# PGA-103_LNA_Mod2.net
KiCad netlist of a schematic drawn in EAGLE
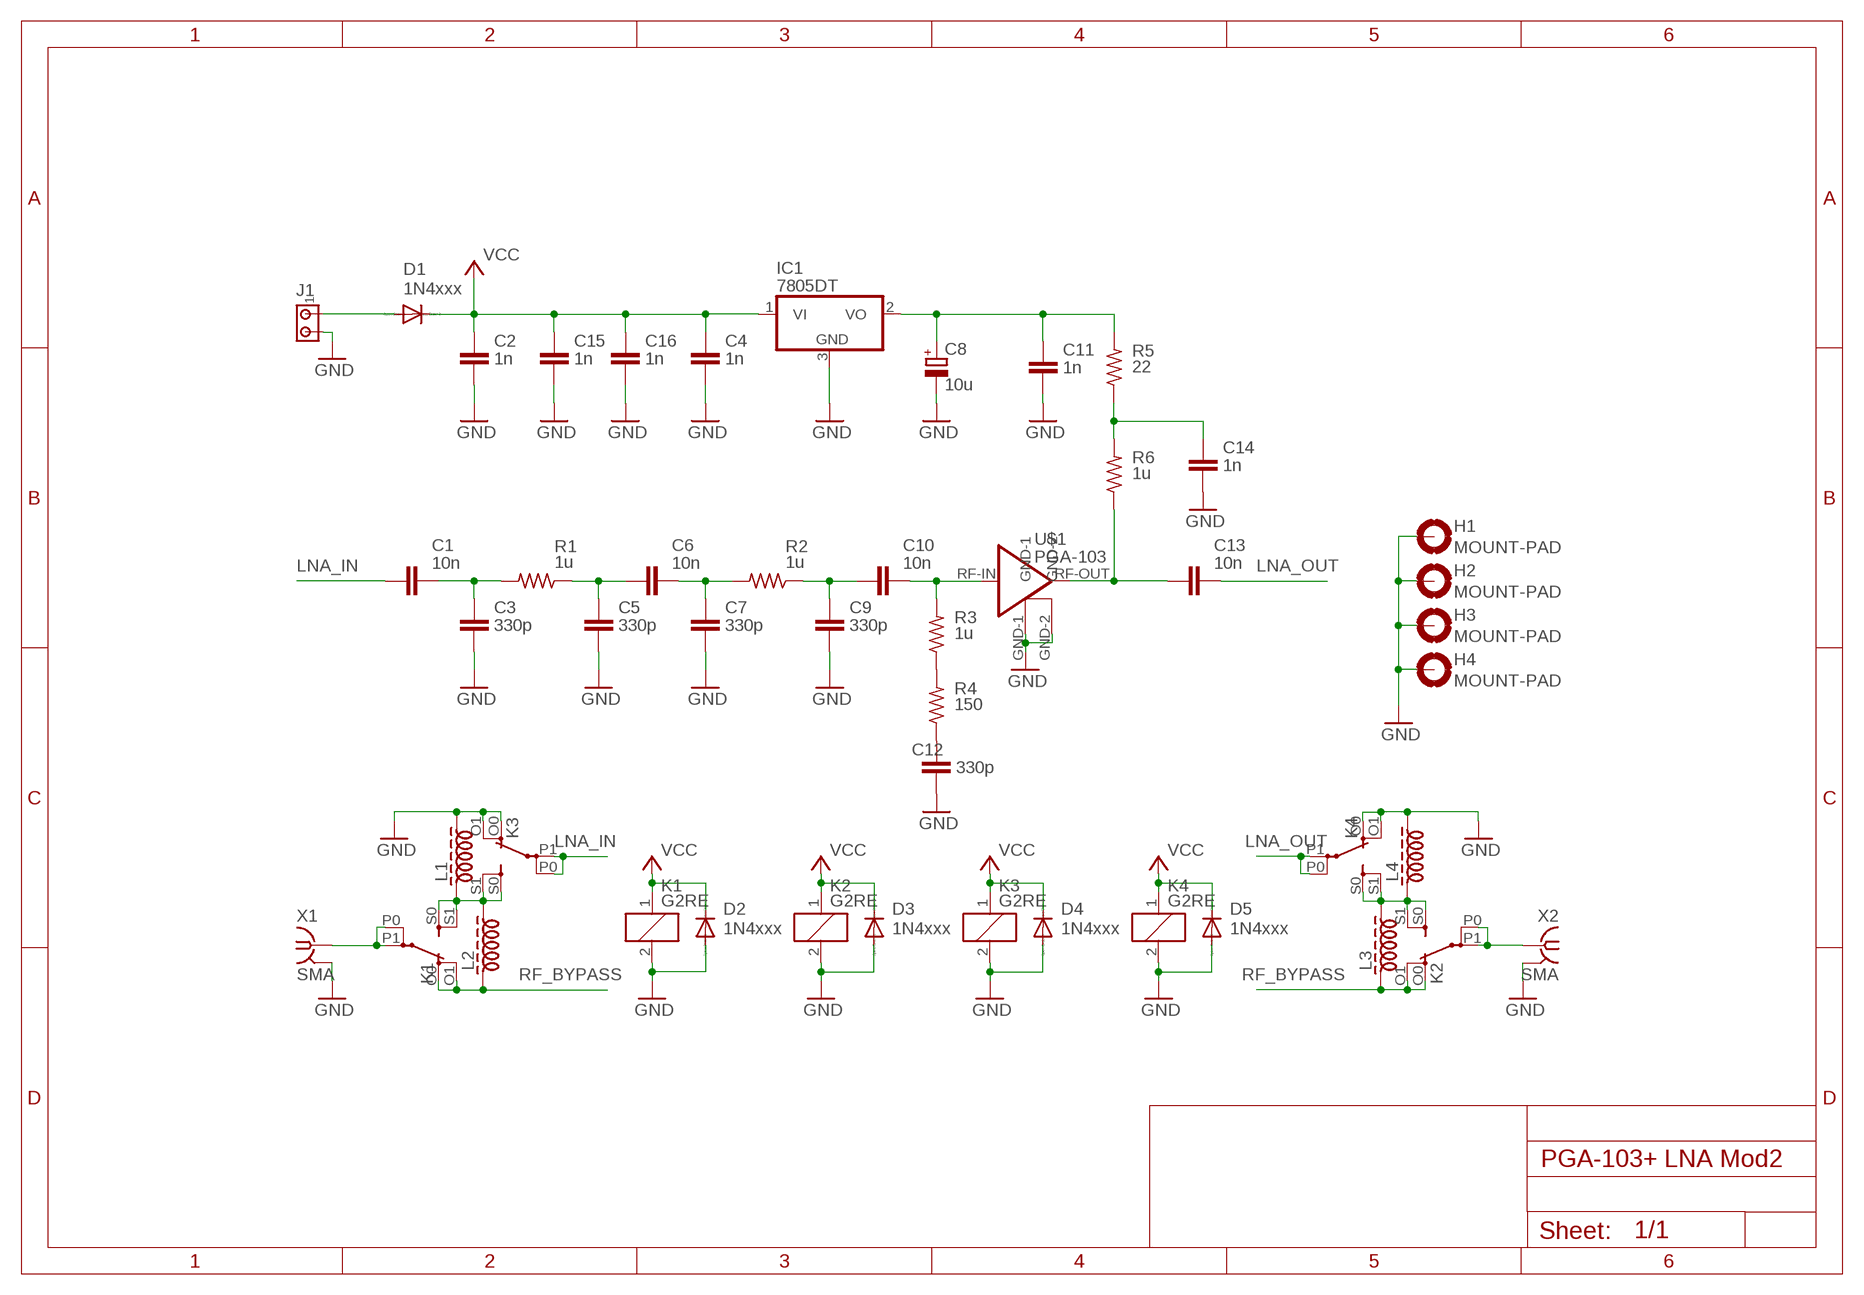
[diagram p0: schematic, sheet 1]

(export (version "E")
  (design (tool "Eeschema 10.0.6"))
  (components
    (comp (ref "C1")
      (value "10n")
      (footprint "eagle-import:C1206")
      (libsource (lib "eagle-import") (part "C-EUC1206"))
    )
    (comp (ref "C2")
      (value "1n")
      (footprint "eagle-import:C1206")
      (libsource (lib "eagle-import") (part "C-EUC1206"))
    )
    (comp (ref "C3")
      (value "330p")
      (footprint "eagle-import:C1206")
      (libsource (lib "eagle-import") (part "C-EUC1206"))
    )
    (comp (ref "C4")
      (value "1n")
      (footprint "eagle-import:C1206")
      (libsource (lib "eagle-import") (part "C-EUC1206"))
    )
    (comp (ref "C5")
      (value "330p")
      (footprint "eagle-import:C1206")
      (libsource (lib "eagle-import") (part "C-EUC1206"))
    )
    (comp (ref "C6")
      (value "10n")
      (footprint "eagle-import:C1206")
      (libsource (lib "eagle-import") (part "C-EUC1206"))
    )
    (comp (ref "C7")
      (value "330p")
      (footprint "eagle-import:C1206")
      (libsource (lib "eagle-import") (part "C-EUC1206"))
    )
    (comp (ref "C8")
      (value "10u")
      (footprint "eagle-import:B_3528-21R")
      (libsource (lib "eagle-import") (part "CPOL-EUB/3528-21R"))
    )
    (comp (ref "C9")
      (value "330p")
      (footprint "eagle-import:C1206")
      (libsource (lib "eagle-import") (part "C-EUC1206"))
    )
    (comp (ref "C10")
      (value "10n")
      (footprint "eagle-import:C1206")
      (libsource (lib "eagle-import") (part "C-EUC1206"))
    )
    (comp (ref "C11")
      (value "1n")
      (footprint "eagle-import:C1206")
      (libsource (lib "eagle-import") (part "C-EUC1206"))
    )
    (comp (ref "C12")
      (value "330p")
      (footprint "eagle-import:C1206")
      (libsource (lib "eagle-import") (part "C-EUC1206"))
    )
    (comp (ref "C13")
      (value "10n")
      (footprint "eagle-import:C1206")
      (libsource (lib "eagle-import") (part "C-EUC1206"))
    )
    (comp (ref "C14")
      (value "1n")
      (footprint "eagle-import:C1206")
      (libsource (lib "eagle-import") (part "C-EUC1206"))
    )
    (comp (ref "C15")
      (value "1n")
      (footprint "eagle-import:C1206")
      (libsource (lib "eagle-import") (part "C-EUC1206"))
    )
    (comp (ref "C16")
      (value "1n")
      (footprint "eagle-import:C1206")
      (libsource (lib "eagle-import") (part "C-EUC1206"))
    )
    (comp (ref "D1")
      (value "1N4xxx")
      (footprint "eagle-import:DO35-7")
      (libsource (lib "eagle-import") (part "1N4148DO35-7"))
    )
    (comp (ref "D2")
      (value "1N4xxx")
      (footprint "eagle-import:DO35-7")
      (libsource (lib "eagle-import") (part "1N4148DO35-7"))
    )
    (comp (ref "D3")
      (value "1N4xxx")
      (footprint "eagle-import:DO35-7")
      (libsource (lib "eagle-import") (part "1N4148DO35-7"))
    )
    (comp (ref "D4")
      (value "1N4xxx")
      (footprint "eagle-import:DO35-7")
      (libsource (lib "eagle-import") (part "1N4148DO35-7"))
    )
    (comp (ref "D5")
      (value "1N4xxx")
      (footprint "eagle-import:DO35-7")
      (libsource (lib "eagle-import") (part "1N4148DO35-7"))
    )
    (comp (ref "H1")
      (value "MOUNT-PAD")
      (footprint "eagle-import:2,8-PAD")
      (libsource (lib "eagle-import") (part "MOUNT-PAD-ROUND2.8"))
    )
    (comp (ref "H2")
      (value "MOUNT-PAD")
      (footprint "eagle-import:2,8-PAD")
      (libsource (lib "eagle-import") (part "MOUNT-PAD-ROUND2.8"))
    )
    (comp (ref "H3")
      (value "MOUNT-PAD")
      (footprint "eagle-import:2,8-PAD")
      (libsource (lib "eagle-import") (part "MOUNT-PAD-ROUND2.8"))
    )
    (comp (ref "H4")
      (value "MOUNT-PAD")
      (footprint "eagle-import:2,8-PAD")
      (libsource (lib "eagle-import") (part "MOUNT-PAD-ROUND2.8"))
    )
    (comp (ref "IC1")
      (value "7805DT")
      (footprint "eagle-import:TO252")
      (libsource (lib "eagle-import") (part "78DT05"))
    )
    (comp (ref "J1")
      (value "MTA02-156")
      (footprint "eagle-import:1X2MTA")
      (libsource (lib "eagle-import") (part "MTA02-156"))
    )
    (comp (ref "K1")
      (value "G2RE")
      (footprint "eagle-import:G2RE")
      (libsource (lib "eagle-import") (part "G2RE"))
    )
    (comp (ref "K2")
      (value "G2RE")
      (footprint "eagle-import:G2RE")
      (libsource (lib "eagle-import") (part "G2RE"))
    )
    (comp (ref "K3")
      (value "G2RE")
      (footprint "eagle-import:G2RE")
      (libsource (lib "eagle-import") (part "G2RE"))
    )
    (comp (ref "K4")
      (value "G2RE")
      (footprint "eagle-import:G2RE")
      (libsource (lib "eagle-import") (part "G2RE"))
    )
    (comp (ref "L1")
      (value "Z28/70CW")
      (footprint "eagle-import:Z28_7")
      (libsource (lib "eagle-import") (part "Z?CW28/70"))
    )
    (comp (ref "L2")
      (value "Z28/70CW")
      (footprint "eagle-import:Z28_7")
      (libsource (lib "eagle-import") (part "Z?CW28/70"))
    )
    (comp (ref "L3")
      (value "Z28/70CW")
      (footprint "eagle-import:Z28_7")
      (libsource (lib "eagle-import") (part "Z?CW28/70"))
    )
    (comp (ref "L4")
      (value "Z28/70CW")
      (footprint "eagle-import:Z28_7")
      (libsource (lib "eagle-import") (part "Z?CW28/70"))
    )
    (comp (ref "R1")
      (value "1u")
      (footprint "eagle-import:M1206")
      (libsource (lib "eagle-import") (part "R-US_M1206"))
    )
    (comp (ref "R2")
      (value "1u")
      (footprint "eagle-import:M1206")
      (libsource (lib "eagle-import") (part "R-US_M1206"))
    )
    (comp (ref "R3")
      (value "1u")
      (footprint "eagle-import:M1206")
      (libsource (lib "eagle-import") (part "R-US_M1206"))
    )
    (comp (ref "R4")
      (value "150")
      (footprint "eagle-import:M1206")
      (libsource (lib "eagle-import") (part "R-US_M1206"))
    )
    (comp (ref "R5")
      (value "22")
      (footprint "eagle-import:M1206")
      (libsource (lib "eagle-import") (part "R-US_M1206"))
    )
    (comp (ref "R6")
      (value "1u")
      (footprint "eagle-import:M1206")
      (libsource (lib "eagle-import") (part "R-US_M1206"))
    )
    (comp (ref "U$1")
      (value "PGA-103")
      (footprint "eagle-import:DF782")
      (libsource (lib "eagle-import") (part "PGA-103"))
    )
    (comp (ref "X1")
      (value "SMA")
      (footprint "eagle-import:J502-ND-142-0701-851_861")
      (fields (field (name "MF") "JOHNSON COMPONENTS") (field (name "MPN") "142-0701-851"))
      (libsource (lib "eagle-import") (part "SMA-142-0701-851/861"))
    )
    (comp (ref "X2")
      (value "SMA")
      (footprint "eagle-import:J502-ND-142-0701-851_861")
      (fields (field (name "MF") "JOHNSON COMPONENTS") (field (name "MPN") "142-0701-851"))
      (libsource (lib "eagle-import") (part "SMA-142-0701-851/861"))
    )
  )
  (nets
    (net (code "1") (name "/LNA_IN") (class "Default")
      (node (ref "C1") (pin "1") (pinfunction "1_1") (pintype "passive"))
      (node (ref "K3") (pin "P0") (pinfunction "P_P0") (pintype "passive"))
      (node (ref "K3") (pin "P1") (pinfunction "P_P1") (pintype "passive"))
    )
    (net (code "2") (name "/LNA_OUT") (class "Default")
      (node (ref "C13") (pin "2") (pinfunction "2_2") (pintype "passive"))
      (node (ref "K4") (pin "P0") (pinfunction "P_P0") (pintype "passive"))
      (node (ref "K4") (pin "P1") (pinfunction "P_P1") (pintype "passive"))
    )
    (net (code "3") (name "/RF_BYPASS") (class "Default")
      (node (ref "K1") (pin "O0") (pinfunction "O_O0") (pintype "passive"))
      (node (ref "K1") (pin "O1") (pinfunction "O_O1") (pintype "passive"))
      (node (ref "K2") (pin "O0") (pinfunction "O_O0") (pintype "passive"))
      (node (ref "K2") (pin "O1") (pinfunction "O_O1") (pintype "passive"))
      (node (ref "L2") (pin "1") (pinfunction "1_1") (pintype "passive"))
      (node (ref "L3") (pin "1") (pinfunction "1_1") (pintype "passive"))
    )
    (net (code "4") (name "GND") (class "Default")
      (node (ref "C11") (pin "2") (pinfunction "2_2") (pintype "passive"))
      (node (ref "C12") (pin "1") (pinfunction "1_1") (pintype "passive"))
      (node (ref "C14") (pin "1") (pinfunction "1_1") (pintype "passive"))
      (node (ref "C15") (pin "2") (pinfunction "2_2") (pintype "passive"))
      (node (ref "C16") (pin "2") (pinfunction "2_2") (pintype "passive"))
      (node (ref "C2") (pin "2") (pinfunction "2_2") (pintype "passive"))
      (node (ref "C3") (pin "1") (pinfunction "1_1") (pintype "passive"))
      (node (ref "C4") (pin "2") (pinfunction "2_2") (pintype "passive"))
      (node (ref "C5") (pin "1") (pinfunction "1_1") (pintype "passive"))
      (node (ref "C7") (pin "1") (pinfunction "1_1") (pintype "passive"))
      (node (ref "C8") (pin "-") (pinfunction "-_-") (pintype "passive"))
      (node (ref "C9") (pin "1") (pinfunction "1_1") (pintype "passive"))
      (node (ref "D2") (pin "A") (pinfunction "A_A") (pintype "passive"))
      (node (ref "D3") (pin "A") (pinfunction "A_A") (pintype "passive"))
      (node (ref "D4") (pin "A") (pinfunction "A_A") (pintype "passive"))
      (node (ref "D5") (pin "A") (pinfunction "A_A") (pintype "passive"))
      (node (ref "H1") (pin "B2,8") (pinfunction "MOUNT_B2,8") (pintype "passive"))
      (node (ref "H2") (pin "B2,8") (pinfunction "MOUNT_B2,8") (pintype "passive"))
      (node (ref "H3") (pin "B2,8") (pinfunction "MOUNT_B2,8") (pintype "passive"))
      (node (ref "H4") (pin "B2,8") (pinfunction "MOUNT_B2,8") (pintype "passive"))
      (node (ref "IC1") (pin "3") (pinfunction "GND_3") (pintype "passive"))
      (node (ref "J1") (pin "2") (pinfunction "2_2") (pintype "passive"))
      (node (ref "K1") (pin "2") (pinfunction "2_2") (pintype "passive"))
      (node (ref "K2") (pin "2") (pinfunction "2_2") (pintype "passive"))
      (node (ref "K3") (pin "2") (pinfunction "2_2") (pintype "passive"))
      (node (ref "K3") (pin "O0") (pinfunction "O_O0") (pintype "passive"))
      (node (ref "K3") (pin "O1") (pinfunction "O_O1") (pintype "passive"))
      (node (ref "K4") (pin "2") (pinfunction "2_2") (pintype "passive"))
      (node (ref "K4") (pin "O0") (pinfunction "O_O0") (pintype "passive"))
      (node (ref "K4") (pin "O1") (pinfunction "O_O1") (pintype "passive"))
      (node (ref "L1") (pin "2") (pinfunction "2_2") (pintype "passive"))
      (node (ref "L4") (pin "2") (pinfunction "2_2") (pintype "passive"))
      (node (ref "U$1") (pin "GND-1") (pinfunction "GND-1_GND-1") (pintype "power_in"))
      (node (ref "U$1") (pin "GND-2") (pinfunction "GND-2_GND-2") (pintype "power_in"))
      (node (ref "X1") (pin "G@1") (pinfunction "2_G@1") (pintype "passive"))
      (node (ref "X1") (pin "G@2") (pinfunction "2_G@2") (pintype "passive"))
      (node (ref "X1") (pin "G@3") (pinfunction "2_G@3") (pintype "passive"))
      (node (ref "X1") (pin "G@4") (pinfunction "2_G@4") (pintype "passive"))
      (node (ref "X2") (pin "G@1") (pinfunction "2_G@1") (pintype "passive"))
      (node (ref "X2") (pin "G@2") (pinfunction "2_G@2") (pintype "passive"))
      (node (ref "X2") (pin "G@3") (pinfunction "2_G@3") (pintype "passive"))
      (node (ref "X2") (pin "G@4") (pinfunction "2_G@4") (pintype "passive"))
    )
    (net (code "5") (name "Net-(C1-Pad2)") (class "Default")
      (node (ref "C1") (pin "2") (pinfunction "2_2") (pintype "passive"))
      (node (ref "C3") (pin "2") (pinfunction "2_2") (pintype "passive"))
      (node (ref "R1") (pin "2") (pinfunction "2_2") (pintype "passive"))
    )
    (net (code "6") (name "Net-(C5-Pad2)") (class "Default")
      (node (ref "C5") (pin "2") (pinfunction "2_2") (pintype "passive"))
      (node (ref "C6") (pin "1") (pinfunction "1_1") (pintype "passive"))
      (node (ref "R1") (pin "1") (pinfunction "1_1") (pintype "passive"))
    )
    (net (code "7") (name "Net-(C6-Pad2)") (class "Default")
      (node (ref "C6") (pin "2") (pinfunction "2_2") (pintype "passive"))
      (node (ref "C7") (pin "2") (pinfunction "2_2") (pintype "passive"))
      (node (ref "R2") (pin "2") (pinfunction "2_2") (pintype "passive"))
    )
    (net (code "8") (name "Net-(C10-Pad1)") (class "Default")
      (node (ref "C10") (pin "1") (pinfunction "1_1") (pintype "passive"))
      (node (ref "C9") (pin "2") (pinfunction "2_2") (pintype "passive"))
      (node (ref "R2") (pin "1") (pinfunction "1_1") (pintype "passive"))
    )
    (net (code "9") (name "Net-(C10-Pad2)") (class "Default")
      (node (ref "C10") (pin "2") (pinfunction "2_2") (pintype "passive"))
      (node (ref "R3") (pin "2") (pinfunction "2_2") (pintype "passive"))
      (node (ref "U$1") (pin "RF-IN") (pinfunction "RF-IN_RF-IN") (pintype "input"))
    )
    (net (code "10") (name "Net-(C12-Pad2)") (class "Default")
      (node (ref "C12") (pin "2") (pinfunction "2_2") (pintype "passive"))
      (node (ref "R4") (pin "1") (pinfunction "1_1") (pintype "passive"))
    )
    (net (code "11") (name "Net-(C13-Pad1)") (class "Default")
      (node (ref "C13") (pin "1") (pinfunction "1_1") (pintype "passive"))
      (node (ref "R6") (pin "1") (pinfunction "1_1") (pintype "passive"))
      (node (ref "U$1") (pin "RF-OUT") (pinfunction "RF-OUT_RF-OUT") (pintype "output"))
    )
    (net (code "12") (name "Net-(C14-Pad2)") (class "Default")
      (node (ref "C14") (pin "2") (pinfunction "2_2") (pintype "passive"))
      (node (ref "R5") (pin "1") (pinfunction "1_1") (pintype "passive"))
      (node (ref "R6") (pin "2") (pinfunction "2_2") (pintype "passive"))
    )
    (net (code "13") (name "Net-(D1-PadA)") (class "Default")
      (node (ref "D1") (pin "A") (pinfunction "A_A") (pintype "passive"))
      (node (ref "J1") (pin "1") (pinfunction "1_1") (pintype "passive"))
    )
    (net (code "14") (name "Net-(IC1-VO)") (class "Default")
      (node (ref "C11") (pin "1") (pinfunction "1_1") (pintype "passive"))
      (node (ref "C8") (pin "+") (pinfunction "+_+") (pintype "passive"))
      (node (ref "IC1") (pin "2") (pinfunction "VO_2") (pintype "passive"))
      (node (ref "R5") (pin "2") (pinfunction "2_2") (pintype "passive"))
    )
    (net (code "15") (name "Net-(K1B-P-PadP0)") (class "Default")
      (node (ref "K1") (pin "P0") (pinfunction "P_P0") (pintype "passive"))
      (node (ref "K1") (pin "P1") (pinfunction "P_P1") (pintype "passive"))
      (node (ref "X1") (pin "1") (pinfunction "1_1") (pintype "passive"))
    )
    (net (code "16") (name "Net-(K1B-S-PadS0)") (class "Default")
      (node (ref "K1") (pin "S0") (pinfunction "S_S0") (pintype "passive"))
      (node (ref "K1") (pin "S1") (pinfunction "S_S1") (pintype "passive"))
      (node (ref "K3") (pin "S0") (pinfunction "S_S0") (pintype "passive"))
      (node (ref "K3") (pin "S1") (pinfunction "S_S1") (pintype "passive"))
      (node (ref "L1") (pin "1") (pinfunction "1_1") (pintype "passive"))
      (node (ref "L2") (pin "2") (pinfunction "2_2") (pintype "passive"))
    )
    (net (code "17") (name "Net-(K2B-P-PadP0)") (class "Default")
      (node (ref "K2") (pin "P0") (pinfunction "P_P0") (pintype "passive"))
      (node (ref "K2") (pin "P1") (pinfunction "P_P1") (pintype "passive"))
      (node (ref "X2") (pin "1") (pinfunction "1_1") (pintype "passive"))
    )
    (net (code "18") (name "Net-(K2B-S-PadS0)") (class "Default")
      (node (ref "K2") (pin "S0") (pinfunction "S_S0") (pintype "passive"))
      (node (ref "K2") (pin "S1") (pinfunction "S_S1") (pintype "passive"))
      (node (ref "K4") (pin "S0") (pinfunction "S_S0") (pintype "passive"))
      (node (ref "K4") (pin "S1") (pinfunction "S_S1") (pintype "passive"))
      (node (ref "L3") (pin "2") (pinfunction "2_2") (pintype "passive"))
      (node (ref "L4") (pin "1") (pinfunction "1_1") (pintype "passive"))
    )
    (net (code "19") (name "Net-(R3-Pad1)") (class "Default")
      (node (ref "R3") (pin "1") (pinfunction "1_1") (pintype "passive"))
      (node (ref "R4") (pin "2") (pinfunction "2_2") (pintype "passive"))
    )
    (net (code "20") (name "VCC") (class "Default")
      (node (ref "C15") (pin "1") (pinfunction "1_1") (pintype "passive"))
      (node (ref "C16") (pin "1") (pinfunction "1_1") (pintype "passive"))
      (node (ref "C2") (pin "1") (pinfunction "1_1") (pintype "passive"))
      (node (ref "C4") (pin "1") (pinfunction "1_1") (pintype "passive"))
      (node (ref "D1") (pin "C") (pinfunction "C_C") (pintype "passive"))
      (node (ref "D2") (pin "C") (pinfunction "C_C") (pintype "passive"))
      (node (ref "D3") (pin "C") (pinfunction "C_C") (pintype "passive"))
      (node (ref "D4") (pin "C") (pinfunction "C_C") (pintype "passive"))
      (node (ref "D5") (pin "C") (pinfunction "C_C") (pintype "passive"))
      (node (ref "IC1") (pin "1") (pinfunction "VI_1") (pintype "input"))
      (node (ref "K1") (pin "1") (pinfunction "1_1") (pintype "passive"))
      (node (ref "K2") (pin "1") (pinfunction "1_1") (pintype "passive"))
      (node (ref "K3") (pin "1") (pinfunction "1_1") (pintype "passive"))
      (node (ref "K4") (pin "1") (pinfunction "1_1") (pintype "passive"))
    )
  )
)
